# BottleNosePrototype.net
KiCad netlist of a schematic drawn in EAGLE
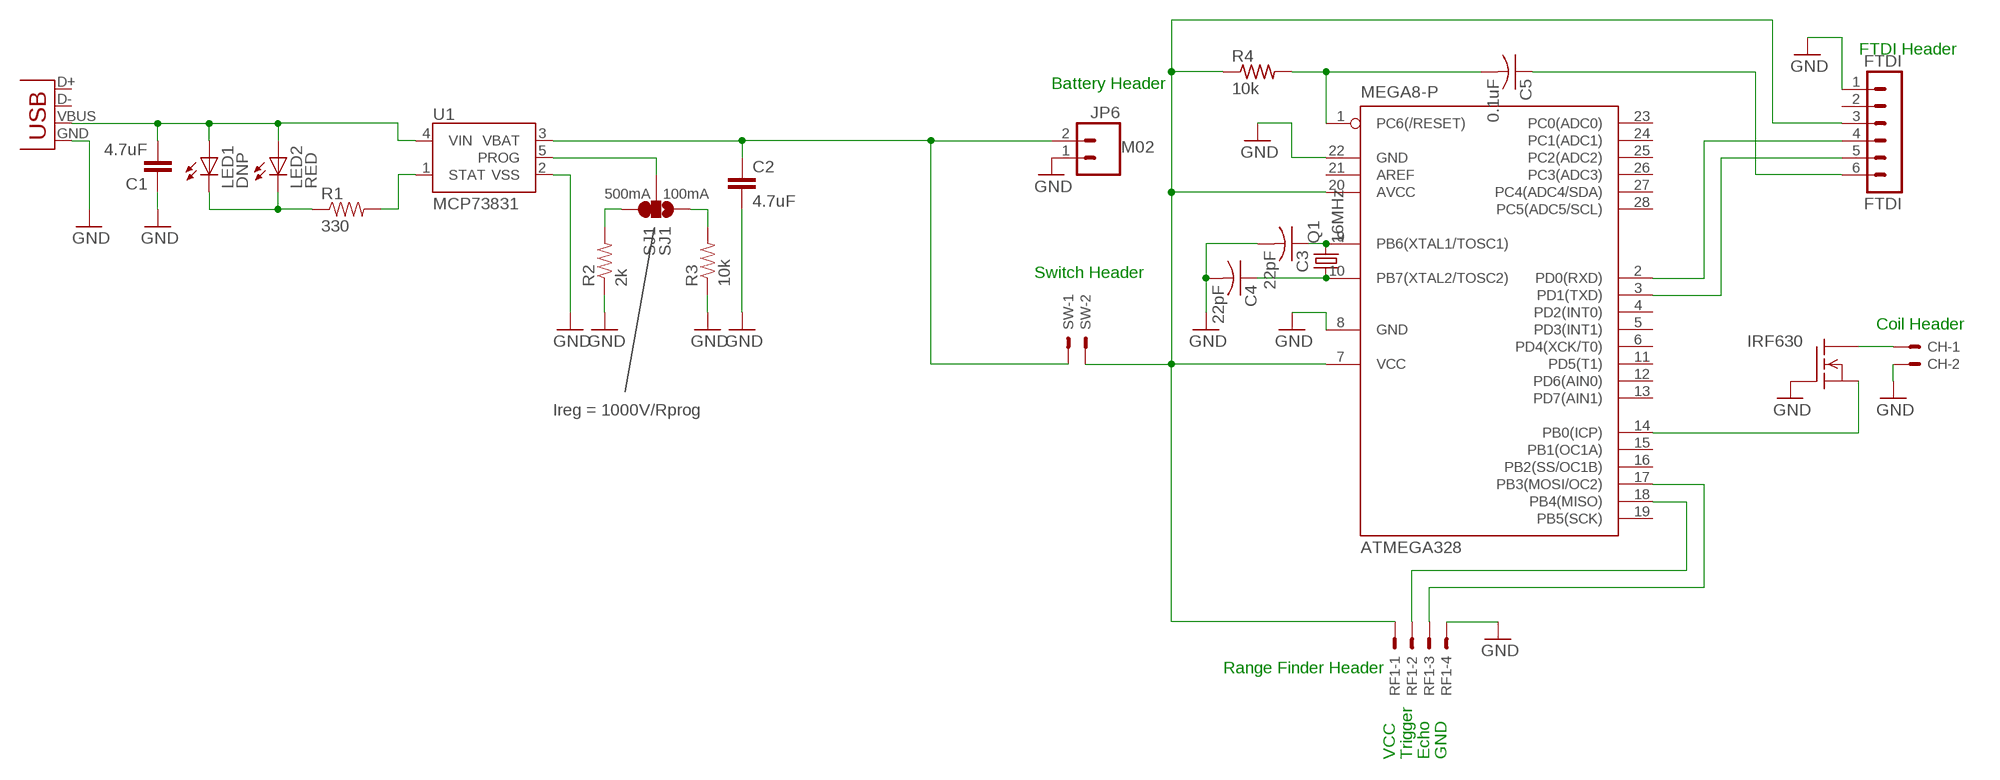
[diagram p0: schematic, sheet 1]

(export (version "E")
  (design (tool "Eeschema 10.0.6"))
  (components
    (comp (ref "ATMEGA328")
      (value "MEGA8-P")
      (footprint "eagle-import:DIL28-3")
      (libsource (lib "eagle-import") (part "MEGA8-P"))
    )
    (comp (ref "C1")
      (value "4.7uF")
      (footprint "eagle-import:0402-CAP")
      (libsource (lib "eagle-import") (part "CAP0402-CAP"))
    )
    (comp (ref "C2")
      (value "4.7uF")
      (footprint "eagle-import:0402-CAP")
      (libsource (lib "eagle-import") (part "CAP0402-CAP"))
    )
    (comp (ref "C3")
      (value "22pF")
      (footprint "eagle-import:C025-024X044")
      (libsource (lib "eagle-import") (part "C-US025-024X044"))
    )
    (comp (ref "C4")
      (value "22pF")
      (footprint "eagle-import:C025-024X044")
      (libsource (lib "eagle-import") (part "C-US025-024X044"))
    )
    (comp (ref "C5")
      (value "0.1uF")
      (footprint "eagle-import:C025-024X044")
      (libsource (lib "eagle-import") (part "C-US025-024X044"))
    )
    (comp (ref "CH")
      (value "22-23-2021")
      (footprint "eagle-import:22-23-2021")
      (fields (field (name "MF") "MOLEX"))
      (libsource (lib "eagle-import") (part "22-23-2021"))
    )
    (comp (ref "FTDI")
      (value "FTDI")
      (footprint "eagle-import:MA06-1")
      (libsource (lib "eagle-import") (part "MA06-1"))
    )
    (comp (ref "IRF630")
      (value "IRF620")
      (footprint "eagle-import:TO220")
      (libsource (lib "eagle-import") (part "IRF620"))
    )
    (comp (ref "JP6")
      (value "M02")
      (footprint "eagle-import:1X02")
      (libsource (lib "eagle-import") (part "M02PTH"))
    )
    (comp (ref "LED1")
      (value "DNP")
      (footprint "eagle-import:LED3MM")
      (libsource (lib "eagle-import") (part "LED3MM"))
    )
    (comp (ref "LED2")
      (value "RED")
      (footprint "eagle-import:LED-0603")
      (libsource (lib "eagle-import") (part "LED0603"))
    )
    (comp (ref "Q1")
      (value "16MHz")
      (footprint "eagle-import:TC26V")
      (libsource (lib "eagle-import") (part "CRYSTALTC26V"))
    )
    (comp (ref "R1")
      (value "330")
      (footprint "eagle-import:0402-RES")
      (libsource (lib "eagle-import") (part "RESISTOR0402-RES"))
    )
    (comp (ref "R2")
      (value "2k")
      (footprint "eagle-import:0402-RES")
      (libsource (lib "eagle-import") (part "RESISTOR0402-RES"))
    )
    (comp (ref "R3")
      (value "10k")
      (footprint "eagle-import:0402-RES")
      (libsource (lib "eagle-import") (part "RESISTOR0402-RES"))
    )
    (comp (ref "R4")
      (value "10k")
      (footprint "eagle-import:0204_5")
      (libsource (lib "eagle-import") (part "R-US_0204/5"))
    )
    (comp (ref "RF1")
      (value "22-23-2041")
      (footprint "eagle-import:22-23-2041")
      (fields (field (name "MF") "MOLEX"))
      (libsource (lib "eagle-import") (part "22-23-2041"))
    )
    (comp (ref "SJ1")
      (value "SJ1")
      (footprint "eagle-import:SJ_3")
      (libsource (lib "eagle-import") (part "SOLDERJUMPER_2WAYS"))
    )
    (comp (ref "SW")
      (value "22-23-2021")
      (footprint "eagle-import:22-23-2021")
      (fields (field (name "MF") "MOLEX"))
      (libsource (lib "eagle-import") (part "22-23-2021"))
    )
    (comp (ref "U1")
      (value "MCP73831")
      (footprint "eagle-import:SOT23-5")
      (libsource (lib "eagle-import") (part "MCP73831"))
    )
    (comp (ref "X2")
      (value "USBSMD")
      (footprint "eagle-import:USB-MINIB")
      (libsource (lib "eagle-import") (part "USBSMD"))
    )
  )
  (nets
    (net (code "1") (name "GND") (class "Default")
      (node (ref "ATMEGA328") (pin "22") (pinfunction "GND_22") (pintype "power_in"))
      (node (ref "ATMEGA328") (pin "8") (pinfunction "GND_8") (pintype "power_in"))
      (node (ref "C1") (pin "1") (pinfunction "1_1") (pintype "passive"))
      (node (ref "C2") (pin "2") (pinfunction "2_2") (pintype "passive"))
      (node (ref "C3") (pin "2") (pinfunction "2_2") (pintype "passive"))
      (node (ref "C4") (pin "2") (pinfunction "2_2") (pintype "passive"))
      (node (ref "CH") (pin "2") (pinfunction "S_2") (pintype "passive"))
      (node (ref "FTDI") (pin "1") (pinfunction "1_1") (pintype "passive"))
      (node (ref "IRF630") (pin "1") (pinfunction "G_1") (pintype "passive"))
      (node (ref "JP6") (pin "1") (pinfunction "1_1") (pintype "passive"))
      (node (ref "R2") (pin "1") (pinfunction "1_1") (pintype "passive"))
      (node (ref "R3") (pin "1") (pinfunction "1_1") (pintype "passive"))
      (node (ref "RF1") (pin "4") (pinfunction "S_4") (pintype "passive"))
      (node (ref "U1") (pin "2") (pinfunction "VSS_2") (pintype "power_in"))
      (node (ref "X2") (pin "GND") (pinfunction "GND_GND") (pintype "bidirectional"))
    )
    (net (code "2") (name "Net-(ATMEGA328-AVCC)") (class "Default")
      (node (ref "ATMEGA328") (pin "20") (pinfunction "AVCC_20") (pintype "power_in"))
      (node (ref "ATMEGA328") (pin "7") (pinfunction "VCC_7") (pintype "power_in"))
      (node (ref "FTDI") (pin "3") (pinfunction "3_3") (pintype "passive"))
      (node (ref "R4") (pin "1") (pinfunction "1_1") (pintype "passive"))
      (node (ref "RF1") (pin "1") (pinfunction "S_1") (pintype "passive"))
      (node (ref "SW") (pin "2") (pinfunction "S_2") (pintype "passive"))
    )
    (net (code "3") (name "Net-(ATMEGA328-PB0(ICP))") (class "Default")
      (node (ref "ATMEGA328") (pin "14") (pinfunction "PB0(ICP)_14") (pintype "bidirectional"))
      (node (ref "IRF630") (pin "3") (pinfunction "S_3") (pintype "passive"))
    )
    (net (code "4") (name "Net-(ATMEGA328-PB3(MOSI{slash}OC2))") (class "Default")
      (node (ref "ATMEGA328") (pin "17") (pinfunction "PB3(MOSI/OC2)_17") (pintype "bidirectional"))
      (node (ref "RF1") (pin "3") (pinfunction "S_3") (pintype "passive"))
    )
    (net (code "5") (name "Net-(ATMEGA328-PB4(MISO))") (class "Default")
      (node (ref "ATMEGA328") (pin "18") (pinfunction "PB4(MISO)_18") (pintype "bidirectional"))
      (node (ref "RF1") (pin "2") (pinfunction "S_2") (pintype "passive"))
    )
    (net (code "6") (name "Net-(ATMEGA328-PB6(XTAL1{slash}TOSC1))") (class "Default")
      (node (ref "ATMEGA328") (pin "9") (pinfunction "PB6(XTAL1/TOSC1)_9") (pintype "bidirectional"))
      (node (ref "C3") (pin "1") (pinfunction "1_1") (pintype "passive"))
      (node (ref "Q1") (pin "2") (pinfunction "2_2") (pintype "passive"))
    )
    (net (code "7") (name "Net-(ATMEGA328-PB7(XTAL2{slash}TOSC2))") (class "Default")
      (node (ref "ATMEGA328") (pin "10") (pinfunction "PB7(XTAL2/TOSC2)_10") (pintype "bidirectional"))
      (node (ref "C4") (pin "1") (pinfunction "1_1") (pintype "passive"))
      (node (ref "Q1") (pin "1") (pinfunction "1_1") (pintype "passive"))
    )
    (net (code "8") (name "Net-(ATMEGA328-PC6({slash}RESET))") (class "Default")
      (node (ref "ATMEGA328") (pin "1") (pinfunction "PC6(/RESET)_1") (pintype "bidirectional"))
      (node (ref "C5") (pin "2") (pinfunction "2_2") (pintype "passive"))
      (node (ref "R4") (pin "2") (pinfunction "2_2") (pintype "passive"))
    )
    (net (code "9") (name "Net-(ATMEGA328-PD0(RXD))") (class "Default")
      (node (ref "ATMEGA328") (pin "2") (pinfunction "PD0(RXD)_2") (pintype "bidirectional"))
      (node (ref "FTDI") (pin "4") (pinfunction "4_4") (pintype "passive"))
    )
    (net (code "10") (name "Net-(ATMEGA328-PD1(TXD))") (class "Default")
      (node (ref "ATMEGA328") (pin "3") (pinfunction "PD1(TXD)_3") (pintype "bidirectional"))
      (node (ref "FTDI") (pin "5") (pinfunction "5_5") (pintype "passive"))
    )
    (net (code "11") (name "Net-(C5-Pad1)") (class "Default")
      (node (ref "C5") (pin "1") (pinfunction "1_1") (pintype "passive"))
      (node (ref "FTDI") (pin "6") (pinfunction "6_6") (pintype "passive"))
    )
    (net (code "12") (name "Net-(CHA-S)") (class "Default")
      (node (ref "CH") (pin "1") (pinfunction "S_1") (pintype "passive"))
      (node (ref "IRF630") (pin "2") (pinfunction "D_2") (pintype "passive"))
    )
    (net (code "13") (name "Net-(LED1-C)") (class "Default")
      (node (ref "LED1") (pin "K") (pinfunction "C_K") (pintype "passive"))
      (node (ref "LED2") (pin "C") (pinfunction "C_C") (pintype "passive"))
      (node (ref "R1") (pin "1") (pinfunction "1_1") (pintype "passive"))
    )
    (net (code "14") (name "Net-(R2-Pad2)") (class "Default")
      (node (ref "R2") (pin "2") (pinfunction "2_2") (pintype "passive"))
      (node (ref "SJ1") (pin "3") (pinfunction "3_3") (pintype "passive"))
    )
    (net (code "15") (name "Net-(R3-Pad2)") (class "Default")
      (node (ref "R3") (pin "2") (pinfunction "2_2") (pintype "passive"))
      (node (ref "SJ1") (pin "1") (pinfunction "1_1") (pintype "passive"))
    )
    (net (code "16") (name "Net-(SWA-S)") (class "Default")
      (node (ref "C2") (pin "1") (pinfunction "1_1") (pintype "passive"))
      (node (ref "JP6") (pin "2") (pinfunction "2_2") (pintype "passive"))
      (node (ref "SW") (pin "1") (pinfunction "S_1") (pintype "passive"))
      (node (ref "U1") (pin "3") (pinfunction "VBAT_3") (pintype "power_in"))
    )
    (net (code "17") (name "Net-(U1-PROG)") (class "Default")
      (node (ref "SJ1") (pin "2") (pinfunction "2_2") (pintype "passive"))
      (node (ref "U1") (pin "5") (pinfunction "PROG_5") (pintype "input"))
    )
    (net (code "18") (name "Net-(U1-STAT)") (class "Default")
      (node (ref "R1") (pin "2") (pinfunction "2_2") (pintype "passive"))
      (node (ref "U1") (pin "1") (pinfunction "STAT_1") (pintype "output"))
    )
    (net (code "19") (name "Net-(U1-VIN)") (class "Default")
      (node (ref "C1") (pin "2") (pinfunction "2_2") (pintype "passive"))
      (node (ref "LED1") (pin "A") (pinfunction "A_A") (pintype "passive"))
      (node (ref "LED2") (pin "A") (pinfunction "A_A") (pintype "passive"))
      (node (ref "U1") (pin "4") (pinfunction "VIN_4") (pintype "power_in"))
      (node (ref "X2") (pin "VBUS") (pinfunction "VBUS_VBUS") (pintype "bidirectional"))
    )
    (net (code "20") (name "unconnected-(ATMEGA328-AREF-Pad21)") (class "Default")
      (node (ref "ATMEGA328") (pin "21") (pinfunction "AREF_21") (pintype "passive"))
    )
    (net (code "21") (name "unconnected-(ATMEGA328-PB1(OC1A)-Pad15)") (class "Default")
      (node (ref "ATMEGA328") (pin "15") (pinfunction "PB1(OC1A)_15") (pintype "bidirectional"))
    )
    (net (code "22") (name "unconnected-(ATMEGA328-PB2(SS{slash}OC1B)-Pad16)") (class "Default")
      (node (ref "ATMEGA328") (pin "16") (pinfunction "PB2(SS/OC1B)_16") (pintype "bidirectional"))
    )
    (net (code "23") (name "unconnected-(ATMEGA328-PB5(SCK)-Pad19)") (class "Default")
      (node (ref "ATMEGA328") (pin "19") (pinfunction "PB5(SCK)_19") (pintype "bidirectional"))
    )
    (net (code "24") (name "unconnected-(ATMEGA328-PC0(ADC0)-Pad23)") (class "Default")
      (node (ref "ATMEGA328") (pin "23") (pinfunction "PC0(ADC0)_23") (pintype "bidirectional"))
    )
    (net (code "25") (name "unconnected-(ATMEGA328-PC1(ADC1)-Pad24)") (class "Default")
      (node (ref "ATMEGA328") (pin "24") (pinfunction "PC1(ADC1)_24") (pintype "bidirectional"))
    )
    (net (code "26") (name "unconnected-(ATMEGA328-PC2(ADC2)-Pad25)") (class "Default")
      (node (ref "ATMEGA328") (pin "25") (pinfunction "PC2(ADC2)_25") (pintype "bidirectional"))
    )
    (net (code "27") (name "unconnected-(ATMEGA328-PC3(ADC3)-Pad26)") (class "Default")
      (node (ref "ATMEGA328") (pin "26") (pinfunction "PC3(ADC3)_26") (pintype "bidirectional"))
    )
    (net (code "28") (name "unconnected-(ATMEGA328-PC4(ADC4{slash}SDA)-Pad27)") (class "Default")
      (node (ref "ATMEGA328") (pin "27") (pinfunction "PC4(ADC4/SDA)_27") (pintype "bidirectional"))
    )
    (net (code "29") (name "unconnected-(ATMEGA328-PC5(ADC5{slash}SCL)-Pad28)") (class "Default")
      (node (ref "ATMEGA328") (pin "28") (pinfunction "PC5(ADC5/SCL)_28") (pintype "bidirectional"))
    )
    (net (code "30") (name "unconnected-(ATMEGA328-PD2(INT0)-Pad4)") (class "Default")
      (node (ref "ATMEGA328") (pin "4") (pinfunction "PD2(INT0)_4") (pintype "bidirectional"))
    )
    (net (code "31") (name "unconnected-(ATMEGA328-PD3(INT1)-Pad5)") (class "Default")
      (node (ref "ATMEGA328") (pin "5") (pinfunction "PD3(INT1)_5") (pintype "bidirectional"))
    )
    (net (code "32") (name "unconnected-(ATMEGA328-PD4(XCK{slash}T0)-Pad6)") (class "Default")
      (node (ref "ATMEGA328") (pin "6") (pinfunction "PD4(XCK/T0)_6") (pintype "bidirectional"))
    )
    (net (code "33") (name "unconnected-(ATMEGA328-PD5(T1)-Pad11)") (class "Default")
      (node (ref "ATMEGA328") (pin "11") (pinfunction "PD5(T1)_11") (pintype "bidirectional"))
    )
    (net (code "34") (name "unconnected-(ATMEGA328-PD6(AIN0)-Pad12)") (class "Default")
      (node (ref "ATMEGA328") (pin "12") (pinfunction "PD6(AIN0)_12") (pintype "bidirectional"))
    )
    (net (code "35") (name "unconnected-(ATMEGA328-PD7(AIN1)-Pad13)") (class "Default")
      (node (ref "ATMEGA328") (pin "13") (pinfunction "PD7(AIN1)_13") (pintype "bidirectional"))
    )
    (net (code "36") (name "unconnected-(FTDI-Pad2)") (class "Default")
      (node (ref "FTDI") (pin "2") (pinfunction "2_2") (pintype "passive"))
    )
    (net (code "37") (name "unconnected-(X2-PadD+)") (class "Default")
      (node (ref "X2") (pin "D+") (pinfunction "D+_D+") (pintype "bidirectional"))
    )
    (net (code "38") (name "unconnected-(X2-PadD-)") (class "Default")
      (node (ref "X2") (pin "D-") (pinfunction "D-_D-") (pintype "bidirectional"))
    )
  )
)
